# MicroMaster.net
KiCad netlist of a schematic drawn in EAGLE
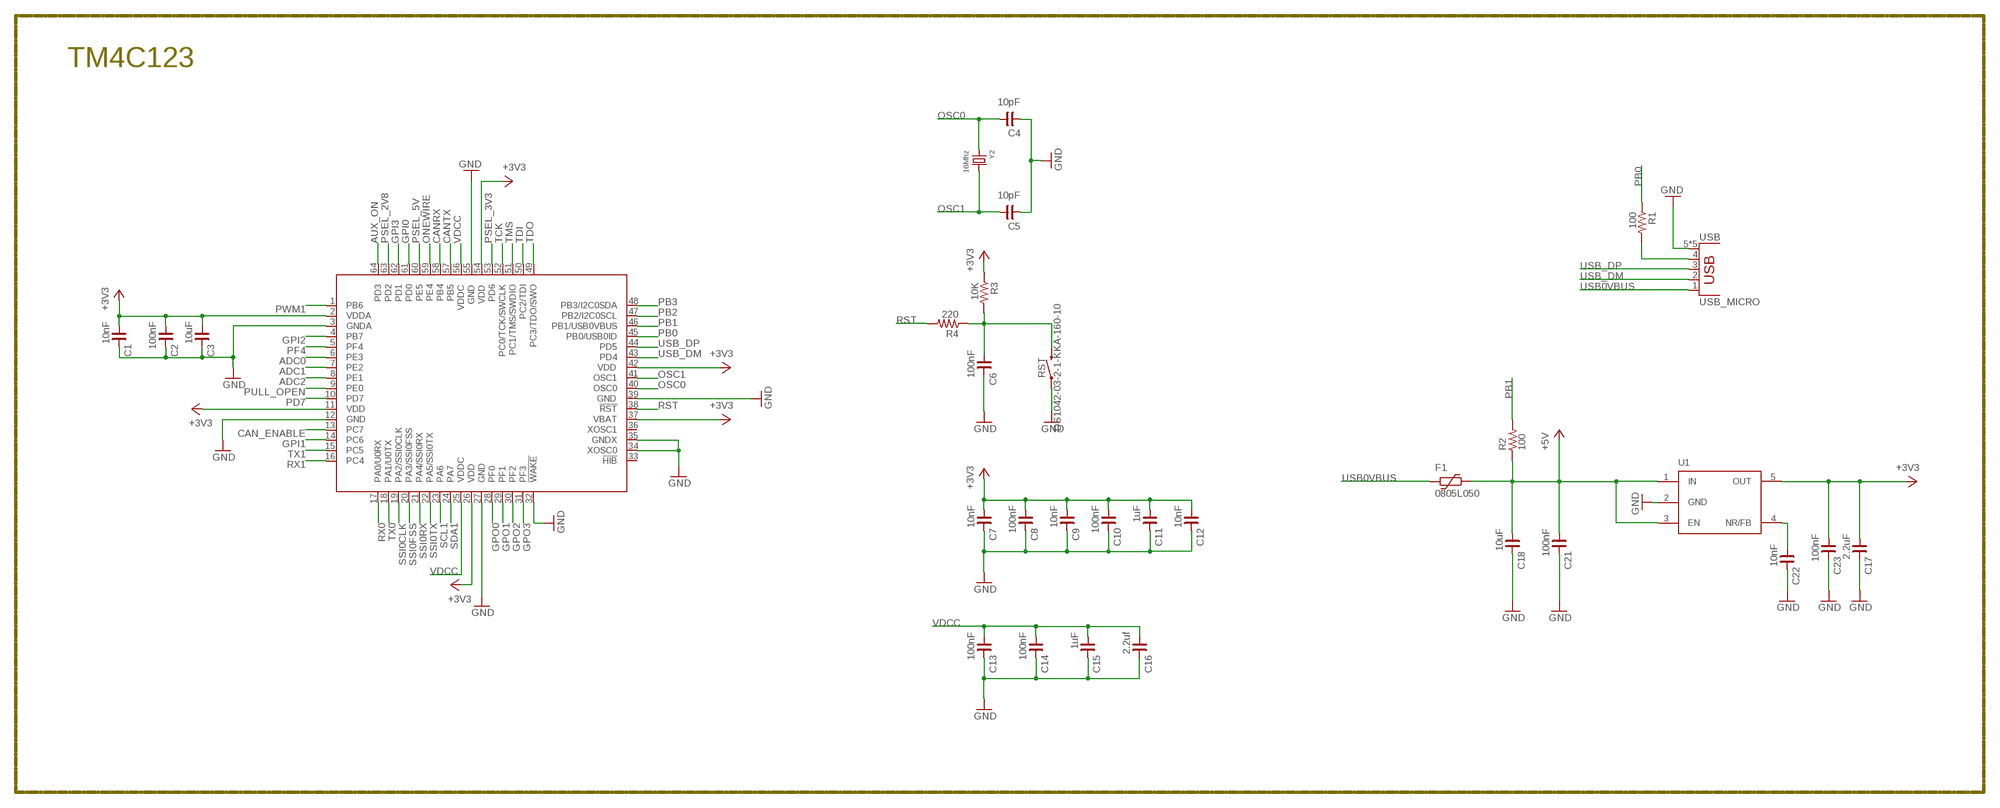
[diagram p0: schematic, sheet 1, part 1 of 3]
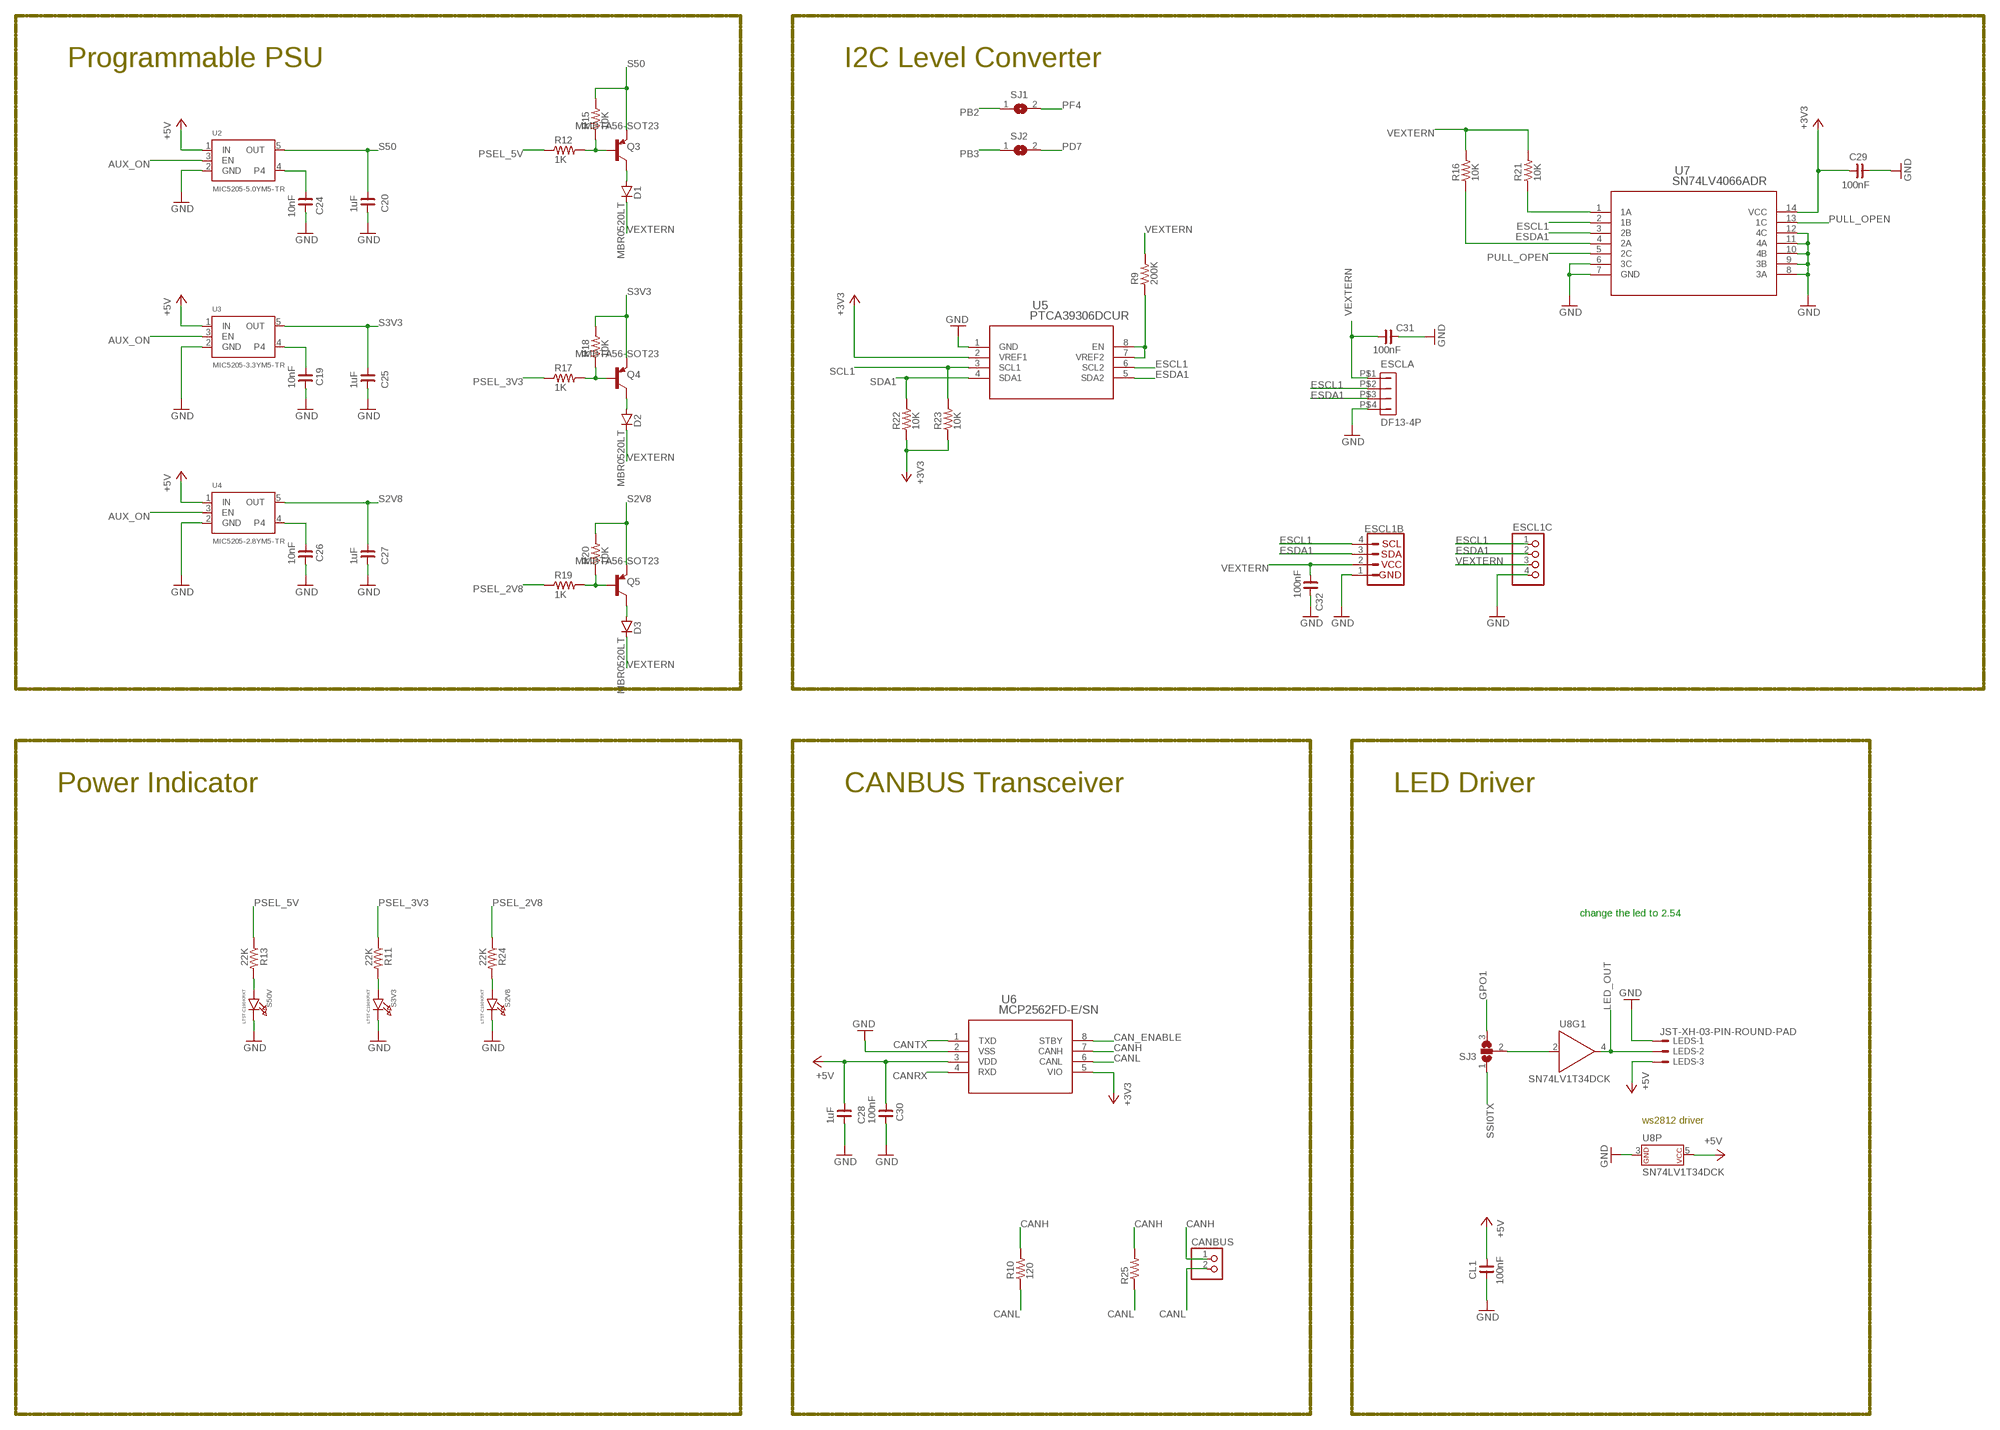
[diagram p1: schematic, sheet 1, part 2 of 3]
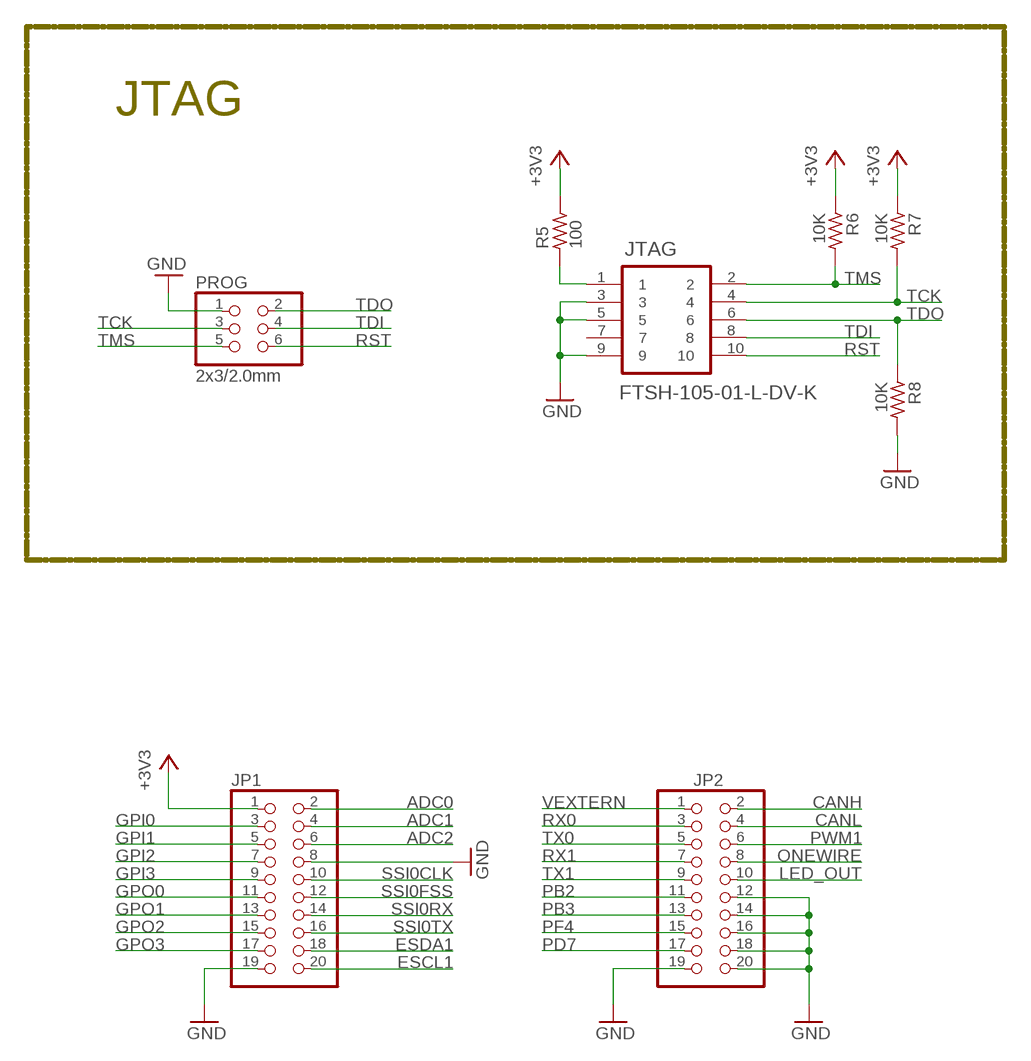
[diagram p2: schematic, sheet 1, part 3 of 3]

(export (version "E")
  (design (tool "Eeschema 10.0.6"))
  (components
    (comp (ref "C1")
      (value "10nF")
      (footprint "eagle-import:C0402")
      (libsource (lib "eagle-import") (part "C_0402"))
    )
    (comp (ref "C2")
      (value "100nF")
      (footprint "eagle-import:C0402")
      (libsource (lib "eagle-import") (part "C_0402"))
    )
    (comp (ref "C3")
      (value "10uF")
      (footprint "eagle-import:C0603")
      (libsource (lib "eagle-import") (part "C_0603"))
    )
    (comp (ref "C4")
      (value "10pF")
      (footprint "eagle-import:C0402")
      (libsource (lib "eagle-import") (part "C_0402"))
    )
    (comp (ref "C5")
      (value "10pF")
      (footprint "eagle-import:C0402")
      (libsource (lib "eagle-import") (part "C_0402"))
    )
    (comp (ref "C6")
      (value "100nF")
      (footprint "eagle-import:C0402")
      (libsource (lib "eagle-import") (part "C_0402"))
    )
    (comp (ref "C7")
      (value "10nF")
      (footprint "eagle-import:C0402")
      (libsource (lib "eagle-import") (part "C_0402"))
    )
    (comp (ref "C8")
      (value "100nF")
      (footprint "eagle-import:C0402")
      (libsource (lib "eagle-import") (part "C_0402"))
    )
    (comp (ref "C9")
      (value "10nF")
      (footprint "eagle-import:C0402")
      (libsource (lib "eagle-import") (part "C_0402"))
    )
    (comp (ref "C10")
      (value "100nF")
      (footprint "eagle-import:C0402")
      (libsource (lib "eagle-import") (part "C_0402"))
    )
    (comp (ref "C11")
      (value "1uF")
      (footprint "eagle-import:C0402")
      (libsource (lib "eagle-import") (part "C_0402"))
    )
    (comp (ref "C12")
      (value "10nF")
      (footprint "eagle-import:C0402")
      (libsource (lib "eagle-import") (part "C_0402"))
    )
    (comp (ref "C13")
      (value "100nF")
      (footprint "eagle-import:C0402")
      (libsource (lib "eagle-import") (part "C_0402"))
    )
    (comp (ref "C14")
      (value "100nF")
      (footprint "eagle-import:C0402")
      (libsource (lib "eagle-import") (part "C_0402"))
    )
    (comp (ref "C15")
      (value "1uF")
      (footprint "eagle-import:C0402")
      (libsource (lib "eagle-import") (part "C_0402"))
    )
    (comp (ref "C16")
      (value "2.2uf")
      (footprint "eagle-import:C0603")
      (libsource (lib "eagle-import") (part "C_0603"))
    )
    (comp (ref "C17")
      (value "2.2uF")
      (footprint "eagle-import:C0603")
      (libsource (lib "eagle-import") (part "C_0603"))
    )
    (comp (ref "C18")
      (value "10uF")
      (footprint "eagle-import:C0603")
      (libsource (lib "eagle-import") (part "C_0603"))
    )
    (comp (ref "C19")
      (value "10nF")
      (footprint "eagle-import:C0402")
      (libsource (lib "eagle-import") (part "C_0402"))
    )
    (comp (ref "C20")
      (value "1uF")
      (footprint "eagle-import:C0603")
      (libsource (lib "eagle-import") (part "C_0603"))
    )
    (comp (ref "C21")
      (value "100nF")
      (footprint "eagle-import:C0402")
      (libsource (lib "eagle-import") (part "C_0402"))
    )
    (comp (ref "C22")
      (value "10nF")
      (footprint "eagle-import:C0402")
      (libsource (lib "eagle-import") (part "C_0402"))
    )
    (comp (ref "C23")
      (value "100nF")
      (footprint "eagle-import:C0402")
      (libsource (lib "eagle-import") (part "C_0402"))
    )
    (comp (ref "C24")
      (value "10nF")
      (footprint "eagle-import:C0402")
      (libsource (lib "eagle-import") (part "C_0402"))
    )
    (comp (ref "C25")
      (value "1uF")
      (footprint "eagle-import:C0603")
      (libsource (lib "eagle-import") (part "C_0603"))
    )
    (comp (ref "C26")
      (value "10nF")
      (footprint "eagle-import:C0402")
      (libsource (lib "eagle-import") (part "C_0402"))
    )
    (comp (ref "C27")
      (value "1uF")
      (footprint "eagle-import:C0603")
      (libsource (lib "eagle-import") (part "C_0603"))
    )
    (comp (ref "C28")
      (value "1uF")
      (footprint "eagle-import:C0805")
      (libsource (lib "eagle-import") (part "C_0805"))
    )
    (comp (ref "C29")
      (value "100nF")
      (footprint "eagle-import:C0603")
      (libsource (lib "eagle-import") (part "C_0603"))
    )
    (comp (ref "C30")
      (value "100nF")
      (footprint "eagle-import:C0603")
      (libsource (lib "eagle-import") (part "C_0603"))
    )
    (comp (ref "C31")
      (value "100nF")
      (footprint "eagle-import:C0402")
      (libsource (lib "eagle-import") (part "C_0402"))
    )
    (comp (ref "C32")
      (value "100nF")
      (footprint "eagle-import:C0402")
      (libsource (lib "eagle-import") (part "C_0402"))
    )
    (comp (ref "CANBUS")
      (value "PINHD-1X02_2.54-S")
      (footprint "eagle-import:1X02-S")
      (libsource (lib "eagle-import") (part "PINHD-1X02_2.54-S"))
    )
    (comp (ref "CL1")
      (value "100nF")
      (footprint "eagle-import:C0402")
      (libsource (lib "eagle-import") (part "C_0402"))
    )
    (comp (ref "D1")
      (value "MBR0520LT")
      (footprint "eagle-import:SOD123")
      (libsource (lib "eagle-import") (part "MBR0520LT"))
    )
    (comp (ref "D2")
      (value "MBR0520LT")
      (footprint "eagle-import:SOD123")
      (libsource (lib "eagle-import") (part "MBR0520LT"))
    )
    (comp (ref "D3")
      (value "MBR0520LT")
      (footprint "eagle-import:SOD123")
      (libsource (lib "eagle-import") (part "MBR0520LT"))
    )
    (comp (ref "ESCL1B")
      (value "QWIIC_CONNECTORJS-1MM")
      (footprint "eagle-import:1X04_1MM_RA")
      (libsource (lib "eagle-import") (part "QWIIC_CONNECTORJS-1MM"))
    )
    (comp (ref "ESCL1C")
      (value "PINHD-1X04_2.54-S")
      (footprint "eagle-import:1X04-S")
      (libsource (lib "eagle-import") (part "PINHD-1X04_2.54-S"))
    )
    (comp (ref "ESCLA")
      (value "DF13-4P")
      (footprint "eagle-import:DF13-4P-1.25DSA")
      (libsource (lib "eagle-import") (part "DF13-4P-1.25DSA"))
    )
    (comp (ref "F1")
      (value "0805L050")
      (footprint "eagle-import:0805L")
      (fields (field (name "MF") "Littelfuse"))
      (libsource (lib "eagle-import") (part "?0805L050"))
    )
    (comp (ref "IC1")
      (value "TM4C123[7,G]XXPM")
      (footprint "eagle-import:PM_S-PQFP-G64")
      (libsource (lib "eagle-import") (part "TM4C123[7,G]XXPM"))
    )
    (comp (ref "JP1")
      (value "PINHD-2X10_2.54")
      (footprint "eagle-import:2X10")
      (libsource (lib "eagle-import") (part "PINHD-2X10_2.54"))
    )
    (comp (ref "JP2")
      (value "PINHD-2X10_2.54")
      (footprint "eagle-import:2X10")
      (libsource (lib "eagle-import") (part "PINHD-2X10_2.54"))
    )
    (comp (ref "JTAG")
      (value "FTSH-105-01-L-DV-K")
      (footprint "eagle-import:SAMTEC_FTSH-105-01-L-DV-K")
      (fields (field (name "MF") "Samtec"))
      (libsource (lib "eagle-import") (part "FTSH-105-01-L-DV-K"))
    )
    (comp (ref "LEDS")
      (value "JST-XH-03-PIN-ROUND-PAD")
      (footprint "eagle-import:JST-XH-03-PACKAGE-ROUND-PAD")
      (libsource (lib "eagle-import") (part "JST-XH-03-PIN-ROUND-PAD"))
    )
    (comp (ref "PROG")
      (value "2x3/2.0mm")
      (footprint "eagle-import:2X03M")
      (libsource (lib "eagle-import") (part "PINHD-2X03_2.00"))
    )
    (comp (ref "Q3")
      (value "MMBTA56-SOT23")
      (footprint "eagle-import:SOT23")
      (libsource (lib "eagle-import") (part "-?SOT23MMBTA56"))
    )
    (comp (ref "Q4")
      (value "MMBTA56-SOT23")
      (footprint "eagle-import:SOT23")
      (libsource (lib "eagle-import") (part "-?SOT23MMBTA56"))
    )
    (comp (ref "Q5")
      (value "MMBTA56-SOT23")
      (footprint "eagle-import:SOT23")
      (libsource (lib "eagle-import") (part "-?SOT23MMBTA56"))
    )
    (comp (ref "R1")
      (value "100")
      (footprint "eagle-import:R0402")
      (libsource (lib "eagle-import") (part "R_0402"))
    )
    (comp (ref "R2")
      (value "100")
      (footprint "eagle-import:R0402")
      (libsource (lib "eagle-import") (part "R_0402"))
    )
    (comp (ref "R3")
      (value "10K")
      (footprint "eagle-import:R0402")
      (libsource (lib "eagle-import") (part "R_0402"))
    )
    (comp (ref "R4")
      (value "220")
      (footprint "eagle-import:R0402")
      (libsource (lib "eagle-import") (part "R_0402"))
    )
    (comp (ref "R5")
      (value "100")
      (footprint "eagle-import:R0402")
      (libsource (lib "eagle-import") (part "R_0402"))
    )
    (comp (ref "R6")
      (value "10K")
      (footprint "eagle-import:R0402")
      (libsource (lib "eagle-import") (part "R_0402"))
    )
    (comp (ref "R7")
      (value "10K")
      (footprint "eagle-import:R0402")
      (libsource (lib "eagle-import") (part "R_0402"))
    )
    (comp (ref "R8")
      (value "10K")
      (footprint "eagle-import:R0402")
      (libsource (lib "eagle-import") (part "R_0402"))
    )
    (comp (ref "R9")
      (value "200K")
      (footprint "eagle-import:R0402")
      (libsource (lib "eagle-import") (part "R_0402"))
    )
    (comp (ref "R10")
      (value "120")
      (footprint "eagle-import:R0603")
      (libsource (lib "eagle-import") (part "R_0603"))
    )
    (comp (ref "R11")
      (value "22K")
      (footprint "eagle-import:R0402")
      (libsource (lib "eagle-import") (part "R_0402"))
    )
    (comp (ref "R12")
      (value "1K")
      (footprint "eagle-import:R0402")
      (libsource (lib "eagle-import") (part "R_0402"))
    )
    (comp (ref "R13")
      (value "22K")
      (footprint "eagle-import:R0402")
      (libsource (lib "eagle-import") (part "R_0402"))
    )
    (comp (ref "R15")
      (value "10K")
      (footprint "eagle-import:R0402")
      (libsource (lib "eagle-import") (part "R_0402"))
    )
    (comp (ref "R16")
      (value "10K")
      (footprint "eagle-import:R0402")
      (libsource (lib "eagle-import") (part "R_0402"))
    )
    (comp (ref "R17")
      (value "1K")
      (footprint "eagle-import:R0402")
      (libsource (lib "eagle-import") (part "R_0402"))
    )
    (comp (ref "R18")
      (value "10K")
      (footprint "eagle-import:R0402")
      (libsource (lib "eagle-import") (part "R_0402"))
    )
    (comp (ref "R19")
      (value "1K")
      (footprint "eagle-import:R0402")
      (libsource (lib "eagle-import") (part "R_0402"))
    )
    (comp (ref "R20")
      (value "10K")
      (footprint "eagle-import:R0402")
      (libsource (lib "eagle-import") (part "R_0402"))
    )
    (comp (ref "R21")
      (value "10K")
      (footprint "eagle-import:R0402")
      (libsource (lib "eagle-import") (part "R_0402"))
    )
    (comp (ref "R22")
      (value "10K")
      (footprint "eagle-import:R0402")
      (libsource (lib "eagle-import") (part "R_0402"))
    )
    (comp (ref "R23")
      (value "10K")
      (footprint "eagle-import:R0402")
      (libsource (lib "eagle-import") (part "R_0402"))
    )
    (comp (ref "R24")
      (value "22K")
      (footprint "eagle-import:R0402")
      (libsource (lib "eagle-import") (part "R_0402"))
    )
    (comp (ref "R25")
      (value "R-US_0204/5")
      (footprint "eagle-import:0204_5")
      (libsource (lib "eagle-import") (part "R-US_0204/5"))
    )
    (comp (ref "RST")
      (value "DS1042-03-2-1-KKA-160-10")
      (footprint "eagle-import:DS1042-03-2-1")
      (libsource (lib "eagle-import") (part "DS1042-03-2-1"))
    )
    (comp (ref "S2V8")
      (value "LTST-C190KRKT")
      (footprint "eagle-import:CHIPLED_0603")
      (libsource (lib "eagle-import") (part "LED0603"))
    )
    (comp (ref "S3V3")
      (value "LTST-C190KRKT")
      (footprint "eagle-import:CHIPLED_0603")
      (libsource (lib "eagle-import") (part "LED0603"))
    )
    (comp (ref "S50V")
      (value "LTST-C190KRKT")
      (footprint "eagle-import:CHIPLED_0603")
      (libsource (lib "eagle-import") (part "LED0603"))
    )
    (comp (ref "SJ1")
      (value "SOLDERJUMPERCLOSED")
      (footprint "eagle-import:SOLDERJUMPER_CLOSEDWIRE")
      (libsource (lib "eagle-import") (part "SOLDERJUMPERCLOSED"))
    )
    (comp (ref "SJ2")
      (value "SOLDERJUMPERCLOSED")
      (footprint "eagle-import:SOLDERJUMPER_CLOSEDWIRE")
      (libsource (lib "eagle-import") (part "SOLDERJUMPERCLOSED"))
    )
    (comp (ref "SJ3")
      (value "SJ2W")
      (footprint "eagle-import:SJ_2")
      (libsource (lib "eagle-import") (part "SJ2W"))
    )
    (comp (ref "U1")
      (value "TPS73633")
      (footprint "eagle-import:SOT23-5L")
      (libsource (lib "eagle-import") (part "TPS73633"))
    )
    (comp (ref "U2")
      (value "MIC5205-5.0YM5-TR")
      (footprint "eagle-import:SOT23-5")
      (libsource (lib "eagle-import") (part "VREG_SOT23-5"))
    )
    (comp (ref "U3")
      (value "MIC5205-3.3YM5-TR")
      (footprint "eagle-import:SOT23-5")
      (libsource (lib "eagle-import") (part "VREG_SOT23-5"))
    )
    (comp (ref "U4")
      (value "MIC5205-2.8YM5-TR")
      (footprint "eagle-import:SOT23-5")
      (libsource (lib "eagle-import") (part "VREG_SOT23-5"))
    )
    (comp (ref "U5")
      (value "PTCA39306DCUR")
      (footprint "eagle-import:VSSOP8_PTCA39306DCUR_TEX")
      (fields (field (name "COPYRIGHT") "Copyright (C) 2021 Ultra Librarian. All rights reserved."))
      (libsource (lib "eagle-import") (part "PTCA39306DCUR"))
    )
    (comp (ref "U6")
      (value "MCP2562FD-E/SN")
      (footprint "eagle-import:SOIC8-N_MC_MCH")
      (fields (field (name "COPYRIGHT") "Copyright (C) 2021 Ultra Librarian. All rights reserved."))
      (libsource (lib "eagle-import") (part "MCP2562FD-E/SN"))
    )
    (comp (ref "U7")
      (value "SN74LV4066ADR")
      (footprint "eagle-import:D14")
      (fields (field (name "COPYRIGHT") "Copyright (C) 2021 Ultra Librarian. All rights reserved."))
      (libsource (lib "eagle-import") (part "SN74LV4066ADR"))
    )
    (comp (ref "U8")
      (value "SN74LV1T34DCK")
      (footprint "eagle-import:SC70-5")
      (libsource (lib "eagle-import") (part "SN74LV1T34DCK"))
    )
    (comp (ref "USB")
      (value "USB_MICRO")
      (footprint "eagle-import:USB_MICRO_MOLEX_FULL")
      (libsource (lib "eagle-import") (part "USB_MICRO"))
    )
    (comp (ref "Y2")
      (value "16Mhz")
      (footprint "eagle-import:6X3.3MM")
      (libsource (lib "eagle-import") (part "CRYSTAL.6X3.3MM"))
    )
  )
  (nets
    (net (code "1") (name "+3V3") (class "Default")
      (node (ref "C1") (pin "1") (pinfunction "1_1") (pintype "passive"))
      (node (ref "C10") (pin "1") (pinfunction "1_1") (pintype "passive"))
      (node (ref "C11") (pin "1") (pinfunction "1_1") (pintype "passive"))
      (node (ref "C12") (pin "1") (pinfunction "1_1") (pintype "passive"))
      (node (ref "C17") (pin "1") (pinfunction "1_1") (pintype "passive"))
      (node (ref "C2") (pin "1") (pinfunction "1_1") (pintype "passive"))
      (node (ref "C23") (pin "1") (pinfunction "1_1") (pintype "passive"))
      (node (ref "C29") (pin "1") (pinfunction "1_1") (pintype "passive"))
      (node (ref "C3") (pin "1") (pinfunction "1_1") (pintype "passive"))
      (node (ref "C7") (pin "1") (pinfunction "1_1") (pintype "passive"))
      (node (ref "C8") (pin "1") (pinfunction "1_1") (pintype "passive"))
      (node (ref "C9") (pin "1") (pinfunction "1_1") (pintype "passive"))
      (node (ref "IC1") (pin "11") (pinfunction "VDD_11") (pintype "bidirectional"))
      (node (ref "IC1") (pin "2") (pinfunction "VDDA_2") (pintype "bidirectional"))
      (node (ref "IC1") (pin "26") (pinfunction "VDD_26") (pintype "bidirectional"))
      (node (ref "IC1") (pin "37") (pinfunction "VBAT_37") (pintype "bidirectional"))
      (node (ref "IC1") (pin "42") (pinfunction "VDD_42") (pintype "bidirectional"))
      (node (ref "IC1") (pin "54") (pinfunction "VDD_54") (pintype "bidirectional"))
      (node (ref "JP1") (pin "1") (pinfunction "1_1") (pintype "passive"))
      (node (ref "R22") (pin "1") (pinfunction "1_1") (pintype "passive"))
      (node (ref "R23") (pin "1") (pinfunction "1_1") (pintype "passive"))
      (node (ref "R3") (pin "1") (pinfunction "1_1") (pintype "passive"))
      (node (ref "R5") (pin "2") (pinfunction "2_2") (pintype "passive"))
      (node (ref "R6") (pin "1") (pinfunction "1_1") (pintype "passive"))
      (node (ref "R7") (pin "1") (pinfunction "1_1") (pintype "passive"))
      (node (ref "U1") (pin "5") (pinfunction "OUT_5") (pintype "bidirectional"))
      (node (ref "U5") (pin "2") (pinfunction "VREF1_2") (pintype "power_in"))
      (node (ref "U6") (pin "5") (pinfunction "VIO_5") (pintype "power_in"))
      (node (ref "U7") (pin "14") (pinfunction "VCC_14") (pintype "power_in"))
    )
    (net (code "2") (name "+5V") (class "Default")
      (node (ref "C18") (pin "1") (pinfunction "1_1") (pintype "passive"))
      (node (ref "C21") (pin "1") (pinfunction "1_1") (pintype "passive"))
      (node (ref "C28") (pin "1") (pinfunction "1_1") (pintype "passive"))
      (node (ref "C30") (pin "1") (pinfunction "1_1") (pintype "passive"))
      (node (ref "CL1") (pin "2") (pinfunction "2_2") (pintype "passive"))
      (node (ref "F1") (pin "1") (pinfunction "1_1") (pintype "passive"))
      (node (ref "LEDS") (pin "3") (pinfunction "S_3") (pintype "passive"))
      (node (ref "R2") (pin "1") (pinfunction "1_1") (pintype "passive"))
      (node (ref "U1") (pin "1") (pinfunction "IN_1") (pintype "bidirectional"))
      (node (ref "U1") (pin "3") (pinfunction "EN_3") (pintype "bidirectional"))
      (node (ref "U2") (pin "1") (pinfunction "IN_1") (pintype "bidirectional"))
      (node (ref "U3") (pin "1") (pinfunction "IN_1") (pintype "bidirectional"))
      (node (ref "U4") (pin "1") (pinfunction "IN_1") (pintype "bidirectional"))
      (node (ref "U6") (pin "3") (pinfunction "VDD_3") (pintype "power_in"))
      (node (ref "U8") (pin "5") (pinfunction "P$V+_5") (pintype "bidirectional"))
    )
    (net (code "3") (name "/ADC0") (class "Default")
      (node (ref "IC1") (pin "6") (pinfunction "PE3_6") (pintype "bidirectional"))
      (node (ref "JP1") (pin "2") (pinfunction "2_2") (pintype "passive"))
    )
    (net (code "4") (name "/ADC1") (class "Default")
      (node (ref "IC1") (pin "7") (pinfunction "PE2_7") (pintype "bidirectional"))
      (node (ref "JP1") (pin "4") (pinfunction "4_4") (pintype "passive"))
    )
    (net (code "5") (name "/ADC2") (class "Default")
      (node (ref "IC1") (pin "8") (pinfunction "PE1_8") (pintype "bidirectional"))
      (node (ref "JP1") (pin "6") (pinfunction "6_6") (pintype "passive"))
    )
    (net (code "6") (name "/AUX_ON") (class "Default")
      (node (ref "IC1") (pin "64") (pinfunction "PD3_64") (pintype "bidirectional"))
      (node (ref "U2") (pin "3") (pinfunction "EN_3") (pintype "bidirectional"))
      (node (ref "U3") (pin "3") (pinfunction "EN_3") (pintype "bidirectional"))
      (node (ref "U4") (pin "3") (pinfunction "EN_3") (pintype "bidirectional"))
    )
    (net (code "7") (name "/CANH") (class "Default")
      (node (ref "CANBUS") (pin "1") (pinfunction "1_1") (pintype "passive"))
      (node (ref "JP2") (pin "2") (pinfunction "2_2") (pintype "passive"))
      (node (ref "R10") (pin "2") (pinfunction "2_2") (pintype "passive"))
      (node (ref "R25") (pin "2") (pinfunction "2_2") (pintype "passive"))
      (node (ref "U6") (pin "7") (pinfunction "CANH_7") (pintype "bidirectional"))
    )
    (net (code "8") (name "/CANL") (class "Default")
      (node (ref "CANBUS") (pin "2") (pinfunction "2_2") (pintype "passive"))
      (node (ref "JP2") (pin "4") (pinfunction "4_4") (pintype "passive"))
      (node (ref "R10") (pin "1") (pinfunction "1_1") (pintype "passive"))
      (node (ref "R25") (pin "1") (pinfunction "1_1") (pintype "passive"))
      (node (ref "U6") (pin "6") (pinfunction "CANL_6") (pintype "bidirectional"))
    )
    (net (code "9") (name "/CANRX") (class "Default")
      (node (ref "IC1") (pin "58") (pinfunction "PB4_58") (pintype "bidirectional"))
      (node (ref "U6") (pin "4") (pinfunction "RXD_4") (pintype "output"))
    )
    (net (code "10") (name "/CANTX") (class "Default")
      (node (ref "IC1") (pin "57") (pinfunction "PB5_57") (pintype "bidirectional"))
      (node (ref "U6") (pin "1") (pinfunction "TXD_1") (pintype "input"))
    )
    (net (code "11") (name "/CAN_ENABLE") (class "Default")
      (node (ref "IC1") (pin "13") (pinfunction "PC7_13") (pintype "bidirectional"))
      (node (ref "U6") (pin "8") (pinfunction "STBY_8") (pintype "input"))
    )
    (net (code "12") (name "/ESCL1") (class "Default")
      (node (ref "ESCL1B") (pin "4") (pinfunction "4_4") (pintype "passive"))
      (node (ref "ESCL1C") (pin "1") (pinfunction "1_1") (pintype "passive"))
      (node (ref "ESCLA") (pin "P$2") (pinfunction "2_P$2") (pintype "passive"))
      (node (ref "JP1") (pin "20") (pinfunction "20_20") (pintype "passive"))
      (node (ref "U5") (pin "6") (pinfunction "SCL2_6") (pintype "bidirectional"))
      (node (ref "U7") (pin "2") (pinfunction "1B_2") (pintype "input"))
    )
    (net (code "13") (name "/ESDA1") (class "Default")
      (node (ref "ESCL1B") (pin "3") (pinfunction "3_3") (pintype "passive"))
      (node (ref "ESCL1C") (pin "2") (pinfunction "2_2") (pintype "passive"))
      (node (ref "ESCLA") (pin "P$3") (pinfunction "3_P$3") (pintype "passive"))
      (node (ref "JP1") (pin "18") (pinfunction "18_18") (pintype "passive"))
      (node (ref "U5") (pin "5") (pinfunction "SDA2_5") (pintype "bidirectional"))
      (node (ref "U7") (pin "3") (pinfunction "2B_3") (pintype "input"))
    )
    (net (code "14") (name "/GPI0") (class "Default")
      (node (ref "IC1") (pin "61") (pinfunction "PD0_61") (pintype "bidirectional"))
      (node (ref "JP1") (pin "3") (pinfunction "3_3") (pintype "passive"))
    )
    (net (code "15") (name "/GPI1") (class "Default")
      (node (ref "IC1") (pin "14") (pinfunction "PC6_14") (pintype "bidirectional"))
      (node (ref "JP1") (pin "5") (pinfunction "5_5") (pintype "passive"))
    )
    (net (code "16") (name "/GPI2") (class "Default")
      (node (ref "IC1") (pin "4") (pinfunction "PB7_4") (pintype "bidirectional"))
      (node (ref "JP1") (pin "7") (pinfunction "7_7") (pintype "passive"))
    )
    (net (code "17") (name "/GPI3") (class "Default")
      (node (ref "IC1") (pin "62") (pinfunction "PD1_62") (pintype "bidirectional"))
      (node (ref "JP1") (pin "9") (pinfunction "9_9") (pintype "passive"))
    )
    (net (code "18") (name "/GPO0") (class "Default")
      (node (ref "IC1") (pin "28") (pinfunction "PF0_28") (pintype "bidirectional"))
      (node (ref "JP1") (pin "11") (pinfunction "11_11") (pintype "passive"))
    )
    (net (code "19") (name "/GPO1") (class "Default")
      (node (ref "IC1") (pin "29") (pinfunction "PF1_29") (pintype "bidirectional"))
      (node (ref "JP1") (pin "13") (pinfunction "13_13") (pintype "passive"))
      (node (ref "SJ3") (pin "3") (pinfunction "3_3") (pintype "passive"))
    )
    (net (code "20") (name "/GPO2") (class "Default")
      (node (ref "IC1") (pin "30") (pinfunction "PF2_30") (pintype "bidirectional"))
      (node (ref "JP1") (pin "15") (pinfunction "15_15") (pintype "passive"))
    )
    (net (code "21") (name "/GPO3") (class "Default")
      (node (ref "IC1") (pin "31") (pinfunction "PF3_31") (pintype "bidirectional"))
      (node (ref "JP1") (pin "17") (pinfunction "17_17") (pintype "passive"))
    )
    (net (code "22") (name "/LED_OUT") (class "Default")
      (node (ref "JP2") (pin "10") (pinfunction "10_10") (pintype "passive"))
      (node (ref "LEDS") (pin "2") (pinfunction "S_2") (pintype "passive"))
      (node (ref "U8") (pin "4") (pinfunction "Y_4") (pintype "bidirectional"))
    )
    (net (code "23") (name "/ONEWIRE") (class "Default")
      (node (ref "IC1") (pin "59") (pinfunction "PE4_59") (pintype "bidirectional"))
      (node (ref "JP2") (pin "8") (pinfunction "8_8") (pintype "passive"))
    )
    (net (code "24") (name "/OSC0") (class "Default")
      (node (ref "C4") (pin "2") (pinfunction "2_2") (pintype "passive"))
      (node (ref "IC1") (pin "40") (pinfunction "OSC0_40") (pintype "bidirectional"))
      (node (ref "Y2") (pin "1") (pinfunction "1_1") (pintype "passive"))
    )
    (net (code "25") (name "/OSC1") (class "Default")
      (node (ref "C5") (pin "2") (pinfunction "2_2") (pintype "passive"))
      (node (ref "IC1") (pin "41") (pinfunction "OSC1_41") (pintype "bidirectional"))
      (node (ref "Y2") (pin "2") (pinfunction "2_2") (pintype "passive"))
    )
    (net (code "26") (name "/PB0") (class "Default")
      (node (ref "IC1") (pin "45") (pinfunction "PB0/USB0ID_45") (pintype "bidirectional"))
      (node (ref "R1") (pin "1") (pinfunction "1_1") (pintype "passive"))
    )
    (net (code "27") (name "/PB1") (class "Default")
      (node (ref "IC1") (pin "46") (pinfunction "PB1/USB0VBUS_46") (pintype "bidirectional"))
      (node (ref "R2") (pin "2") (pinfunction "2_2") (pintype "passive"))
    )
    (net (code "28") (name "/PB2") (class "Default")
      (node (ref "IC1") (pin "47") (pinfunction "PB2/I2C0SCL_47") (pintype "bidirectional"))
      (node (ref "JP2") (pin "11") (pinfunction "11_11") (pintype "passive"))
      (node (ref "SJ1") (pin "1") (pinfunction "1_1") (pintype "passive"))
    )
    (net (code "29") (name "/PB3") (class "Default")
      (node (ref "IC1") (pin "48") (pinfunction "PB3/I2C0SDA_48") (pintype "bidirectional"))
      (node (ref "JP2") (pin "13") (pinfunction "13_13") (pintype "passive"))
      (node (ref "SJ2") (pin "1") (pinfunction "1_1") (pintype "passive"))
    )
    (net (code "30") (name "/PD7") (class "Default")
      (node (ref "IC1") (pin "10") (pinfunction "PD7_10") (pintype "bidirectional"))
      (node (ref "JP2") (pin "17") (pinfunction "17_17") (pintype "passive"))
      (node (ref "SJ2") (pin "2") (pinfunction "2_2") (pintype "passive"))
    )
    (net (code "31") (name "/PF4") (class "Default")
      (node (ref "IC1") (pin "5") (pinfunction "PF4_5") (pintype "bidirectional"))
      (node (ref "JP2") (pin "15") (pinfunction "15_15") (pintype "passive"))
      (node (ref "SJ1") (pin "2") (pinfunction "2_2") (pintype "passive"))
    )
    (net (code "32") (name "/PSEL_2V8") (class "Default")
      (node (ref "IC1") (pin "63") (pinfunction "PD2_63") (pintype "bidirectional"))
      (node (ref "R19") (pin "1") (pinfunction "1_1") (pintype "passive"))
      (node (ref "R24") (pin "1") (pinfunction "1_1") (pintype "passive"))
    )
    (net (code "33") (name "/PSEL_3V3") (class "Default")
      (node (ref "IC1") (pin "53") (pinfunction "PD6_53") (pintype "bidirectional"))
      (node (ref "R11") (pin "1") (pinfunction "1_1") (pintype "passive"))
      (node (ref "R17") (pin "1") (pinfunction "1_1") (pintype "passive"))
    )
    (net (code "34") (name "/PSEL_5V") (class "Default")
      (node (ref "IC1") (pin "60") (pinfunction "PE5_60") (pintype "bidirectional"))
      (node (ref "R12") (pin "1") (pinfunction "1_1") (pintype "passive"))
      (node (ref "R13") (pin "1") (pinfunction "1_1") (pintype "passive"))
    )
    (net (code "35") (name "/PULL_OPEN") (class "Default")
      (node (ref "IC1") (pin "9") (pinfunction "PE0_9") (pintype "bidirectional"))
      (node (ref "U7") (pin "13") (pinfunction "1C_13") (pintype "input"))
      (node (ref "U7") (pin "5") (pinfunction "2C_5") (pintype "input"))
    )
    (net (code "36") (name "/PWM1") (class "Default")
      (node (ref "IC1") (pin "1") (pinfunction "PB6_1") (pintype "bidirectional"))
      (node (ref "JP2") (pin "6") (pinfunction "6_6") (pintype "passive"))
    )
    (net (code "37") (name "/RST") (class "Default")
      (node (ref "IC1") (pin "38") (pinfunction "~{RST}_38") (pintype "bidirectional"))
      (node (ref "JTAG") (pin "10") (pinfunction "10_10") (pintype "passive"))
      (node (ref "PROG") (pin "6") (pinfunction "6_6") (pintype "passive"))
      (node (ref "R4") (pin "2") (pinfunction "2_2") (pintype "passive"))
    )
    (net (code "38") (name "/RX0") (class "Default")
      (node (ref "IC1") (pin "17") (pinfunction "PA0/U0RX_17") (pintype "bidirectional"))
      (node (ref "JP2") (pin "3") (pinfunction "3_3") (pintype "passive"))
    )
    (net (code "39") (name "/RX1") (class "Default")
      (node (ref "IC1") (pin "16") (pinfunction "PC4_16") (pintype "bidirectional"))
      (node (ref "JP2") (pin "7") (pinfunction "7_7") (pintype "passive"))
    )
    (net (code "40") (name "/S2V8") (class "Default")
      (node (ref "C27") (pin "1") (pinfunction "1_1") (pintype "passive"))
      (node (ref "Q5") (pin "2") (pinfunction "E_2") (pintype "passive"))
      (node (ref "R20") (pin "2") (pinfunction "2_2") (pintype "passive"))
      (node (ref "U4") (pin "5") (pinfunction "OUT_5") (pintype "bidirectional"))
    )
    (net (code "41") (name "/S3V3") (class "Default")
      (node (ref "C25") (pin "1") (pinfunction "1_1") (pintype "passive"))
      (node (ref "Q4") (pin "2") (pinfunction "E_2") (pintype "passive"))
      (node (ref "R18") (pin "2") (pinfunction "2_2") (pintype "passive"))
      (node (ref "U3") (pin "5") (pinfunction "OUT_5") (pintype "bidirectional"))
    )
    (net (code "42") (name "/S50") (class "Default")
      (node (ref "C20") (pin "1") (pinfunction "1_1") (pintype "passive"))
      (node (ref "Q3") (pin "2") (pinfunction "E_2") (pintype "passive"))
      (node (ref "R15") (pin "2") (pinfunction "2_2") (pintype "passive"))
      (node (ref "U2") (pin "5") (pinfunction "OUT_5") (pintype "bidirectional"))
    )
    (net (code "43") (name "/SCL1") (class "Default")
      (node (ref "IC1") (pin "23") (pinfunction "PA6_23") (pintype "bidirectional"))
      (node (ref "R23") (pin "2") (pinfunction "2_2") (pintype "passive"))
      (node (ref "U5") (pin "3") (pinfunction "SCL1_3") (pintype "bidirectional"))
    )
    (net (code "44") (name "/SDA1") (class "Default")
      (node (ref "IC1") (pin "24") (pinfunction "PA7_24") (pintype "bidirectional"))
      (node (ref "R22") (pin "2") (pinfunction "2_2") (pintype "passive"))
      (node (ref "U5") (pin "4") (pinfunction "SDA1_4") (pintype "bidirectional"))
    )
    (net (code "45") (name "/SSI0CLK") (class "Default")
      (node (ref "IC1") (pin "19") (pinfunction "PA2/SSI0CLK_19") (pintype "bidirectional"))
      (node (ref "JP1") (pin "10") (pinfunction "10_10") (pintype "passive"))
    )
    (net (code "46") (name "/SSI0FSS") (class "Default")
      (node (ref "IC1") (pin "20") (pinfunction "PA3/SSI0FSS_20") (pintype "bidirectional"))
      (node (ref "JP1") (pin "12") (pinfunction "12_12") (pintype "passive"))
    )
    (net (code "47") (name "/SSI0RX") (class "Default")
      (node (ref "IC1") (pin "21") (pinfunction "PA4/SSI0RX_21") (pintype "bidirectional"))
      (node (ref "JP1") (pin "14") (pinfunction "14_14") (pintype "passive"))
    )
    (net (code "48") (name "/SSI0TX") (class "Default")
      (node (ref "IC1") (pin "22") (pinfunction "PA5/SSI0TX_22") (pintype "bidirectional"))
      (node (ref "JP1") (pin "16") (pinfunction "16_16") (pintype "passive"))
      (node (ref "SJ3") (pin "1") (pinfunction "1_1") (pintype "passive"))
    )
    (net (code "49") (name "/TCK") (class "Default")
      (node (ref "IC1") (pin "52") (pinfunction "PC0/TCK/SWCLK_52") (pintype "bidirectional"))
      (node (ref "JTAG") (pin "4") (pinfunction "4_4") (pintype "passive"))
      (node (ref "PROG") (pin "3") (pinfunction "3_3") (pintype "passive"))
      (node (ref "R7") (pin "2") (pinfunction "2_2") (pintype "passive"))
    )
    (net (code "50") (name "/TDI") (class "Default")
      (node (ref "IC1") (pin "50") (pinfunction "PC2/TDI_50") (pintype "bidirectional"))
      (node (ref "JTAG") (pin "8") (pinfunction "8_8") (pintype "passive"))
      (node (ref "PROG") (pin "4") (pinfunction "4_4") (pintype "passive"))
    )
    (net (code "51") (name "/TDO") (class "Default")
      (node (ref "IC1") (pin "49") (pinfunction "PC3/TDO/SWO_49") (pintype "bidirectional"))
      (node (ref "JTAG") (pin "6") (pinfunction "6_6") (pintype "passive"))
      (node (ref "PROG") (pin "2") (pinfunction "2_2") (pintype "passive"))
      (node (ref "R8") (pin "1") (pinfunction "1_1") (pintype "passive"))
    )
    (net (code "52") (name "/TMS") (class "Default")
      (node (ref "IC1") (pin "51") (pinfunction "PC1/TMS/SWDIO_51") (pintype "bidirectional"))
      (node (ref "JTAG") (pin "2") (pinfunction "2_2") (pintype "passive"))
      (node (ref "PROG") (pin "5") (pinfunction "5_5") (pintype "passive"))
      (node (ref "R6") (pin "2") (pinfunction "2_2") (pintype "passive"))
    )
    (net (code "53") (name "/TX0") (class "Default")
      (node (ref "IC1") (pin "18") (pinfunction "PA1/U0TX_18") (pintype "bidirectional"))
      (node (ref "JP2") (pin "5") (pinfunction "5_5") (pintype "passive"))
    )
    (net (code "54") (name "/TX1") (class "Default")
      (node (ref "IC1") (pin "15") (pinfunction "PC5_15") (pintype "bidirectional"))
      (node (ref "JP2") (pin "9") (pinfunction "9_9") (pintype "passive"))
    )
    (net (code "55") (name "/USB0VBUS") (class "Default")
      (node (ref "F1") (pin "2") (pinfunction "2_2") (pintype "passive"))
      (node (ref "USB") (pin "1") (pinfunction "VBUS_1") (pintype "bidirectional"))
    )
    (net (code "56") (name "/USB_DM") (class "Default")
      (node (ref "IC1") (pin "43") (pinfunction "PD4_43") (pintype "bidirectional"))
      (node (ref "USB") (pin "2") (pinfunction "D-_2") (pintype "bidirectional"))
    )
    (net (code "57") (name "/USB_DP") (class "Default")
      (node (ref "IC1") (pin "44") (pinfunction "PD5_44") (pintype "bidirectional"))
      (node (ref "USB") (pin "3") (pinfunction "D+_3") (pintype "bidirectional"))
    )
    (net (code "58") (name "/VDCC") (class "Default")
      (node (ref "C13") (pin "1") (pinfunction "1_1") (pintype "passive"))
      (node (ref "C14") (pin "1") (pinfunction "1_1") (pintype "passive"))
      (node (ref "C15") (pin "1") (pinfunction "1_1") (pintype "passive"))
      (node (ref "C16") (pin "1") (pinfunction "1_1") (pintype "passive"))
      (node (ref "IC1") (pin "25") (pinfunction "VDDC_25") (pintype "bidirectional"))
      (node (ref "IC1") (pin "56") (pinfunction "VDDC_56") (pintype "bidirectional"))
    )
    (net (code "59") (name "/VEXTERN") (class "Default")
      (node (ref "C31") (pin "1") (pinfunction "1_1") (pintype "passive"))
      (node (ref "C32") (pin "1") (pinfunction "1_1") (pintype "passive"))
      (node (ref "D1") (pin "C") (pinfunction "C_C") (pintype "passive"))
      (node (ref "D2") (pin "C") (pinfunction "C_C") (pintype "passive"))
      (node (ref "D3") (pin "C") (pinfunction "C_C") (pintype "passive"))
      (node (ref "ESCL1B") (pin "2") (pinfunction "2_2") (pintype "power_in"))
      (node (ref "ESCL1C") (pin "3") (pinfunction "3_3") (pintype "passive"))
      (node (ref "ESCLA") (pin "P$1") (pinfunction "1_P$1") (pintype "passive"))
      (node (ref "JP2") (pin "1") (pinfunction "1_1") (pintype "passive"))
      (node (ref "R16") (pin "2") (pinfunction "2_2") (pintype "passive"))
      (node (ref "R21") (pin "2") (pinfunction "2_2") (pintype "passive"))
      (node (ref "R9") (pin "2") (pinfunction "2_2") (pintype "passive"))
    )
    (net (code "60") (name "GND") (class "Default")
      (node (ref "C1") (pin "2") (pinfunction "2_2") (pintype "passive"))
      (node (ref "C10") (pin "2") (pinfunction "2_2") (pintype "passive"))
      (node (ref "C11") (pin "2") (pinfunction "2_2") (pintype "passive"))
      (node (ref "C12") (pin "2") (pinfunction "2_2") (pintype "passive"))
      (node (ref "C13") (pin "2") (pinfunction "2_2") (pintype "passive"))
      (node (ref "C14") (pin "2") (pinfunction "2_2") (pintype "passive"))
      (node (ref "C15") (pin "2") (pinfunction "2_2") (pintype "passive"))
      (node (ref "C16") (pin "2") (pinfunction "2_2") (pintype "passive"))
      (node (ref "C17") (pin "2") (pinfunction "2_2") (pintype "passive"))
      (node (ref "C18") (pin "2") (pinfunction "2_2") (pintype "passive"))
      (node (ref "C19") (pin "2") (pinfunction "2_2") (pintype "passive"))
      (node (ref "C2") (pin "2") (pinfunction "2_2") (pintype "passive"))
      (node (ref "C20") (pin "2") (pinfunction "2_2") (pintype "passive"))
      (node (ref "C21") (pin "2") (pinfunction "2_2") (pintype "passive"))
      (node (ref "C22") (pin "2") (pinfunction "2_2") (pintype "passive"))
      (node (ref "C23") (pin "2") (pinfunction "2_2") (pintype "passive"))
      (node (ref "C24") (pin "2") (pinfunction "2_2") (pintype "passive"))
      (node (ref "C25") (pin "2") (pinfunction "2_2") (pintype "passive"))
      (node (ref "C26") (pin "2") (pinfunction "2_2") (pintype "passive"))
      (node (ref "C27") (pin "2") (pinfunction "2_2") (pintype "passive"))
      (node (ref "C28") (pin "2") (pinfunction "2_2") (pintype "passive"))
      (node (ref "C29") (pin "2") (pinfunction "2_2") (pintype "passive"))
      (node (ref "C3") (pin "2") (pinfunction "2_2") (pintype "passive"))
      (node (ref "C30") (pin "2") (pinfunction "2_2") (pintype "passive"))
      (node (ref "C31") (pin "2") (pinfunction "2_2") (pintype "passive"))
      (node (ref "C32") (pin "2") (pinfunction "2_2") (pintype "passive"))
      (node (ref "C4") (pin "1") (pinfunction "1_1") (pintype "passive"))
      (node (ref "C5") (pin "1") (pinfunction "1_1") (pintype "passive"))
      (node (ref "C6") (pin "2") (pinfunction "2_2") (pintype "passive"))
      (node (ref "C7") (pin "2") (pinfunction "2_2") (pintype "passive"))
      (node (ref "C8") (pin "2") (pinfunction "2_2") (pintype "passive"))
      (node (ref "C9") (pin "2") (pinfunction "2_2") (pintype "passive"))
      (node (ref "CL1") (pin "1") (pinfunction "1_1") (pintype "passive"))
      (node (ref "ESCL1B") (pin "1") (pinfunction "1_1") (pintype "power_in"))
      (node (ref "ESCL1C") (pin "4") (pinfunction "4_4") (pintype "passive"))
      (node (ref "ESCLA") (pin "P$4") (pinfunction "4_P$4") (pintype "passive"))
      (node (ref "IC1") (pin "12") (pinfunction "GND_12") (pintype "bidirectional"))
      (node (ref "IC1") (pin "27") (pinfunction "GND_27") (pintype "bidirectional"))
      (node (ref "IC1") (pin "3") (pinfunction "GNDA_3") (pintype "bidirectional"))
      (node (ref "IC1") (pin "32") (pinfunction "~{WAKE}_32") (pintype "bidirectional"))
      (node (ref "IC1") (pin "34") (pinfunction "XOSC0_34") (pintype "bidirectional"))
      (node (ref "IC1") (pin "35") (pinfunction "GNDX_35") (pintype "bidirectional"))
      (node (ref "IC1") (pin "39") (pinfunction "GND_39") (pintype "bidirectional"))
      (node (ref "IC1") (pin "55") (pinfunction "GND_55") (pintype "bidirectional"))
      (node (ref "JP1") (pin "19") (pinfunction "19_19") (pintype "passive"))
      (node (ref "JP1") (pin "8") (pinfunction "8_8") (pintype "passive"))
      (node (ref "JP2") (pin "12") (pinfunction "12_12") (pintype "passive"))
      (node (ref "JP2") (pin "14") (pinfunction "14_14") (pintype "passive"))
      (node (ref "JP2") (pin "16") (pinfunction "16_16") (pintype "passive"))
      (node (ref "JP2") (pin "18") (pinfunction "18_18") (pintype "passive"))
      (node (ref "JP2") (pin "19") (pinfunction "19_19") (pintype "passive"))
      (node (ref "JP2") (pin "20") (pinfunction "20_20") (pintype "passive"))
      (node (ref "JTAG") (pin "3") (pinfunction "3_3") (pintype "passive"))
      (node (ref "JTAG") (pin "5") (pinfunction "5_5") (pintype "passive"))
      (node (ref "JTAG") (pin "9") (pinfunction "9_9") (pintype "passive"))
      (node (ref "LEDS") (pin "1") (pinfunction "S_1") (pintype "passive"))
      (node (ref "PROG") (pin "1") (pinfunction "1_1") (pintype "passive"))
      (node (ref "R8") (pin "2") (pinfunction "2_2") (pintype "passive"))
      (node (ref "RST") (pin "P$1") (pinfunction "1_P$1") (pintype "passive"))
      (node (ref "S2V8") (pin "C") (pinfunction "C_C") (pintype "passive"))
      (node (ref "S3V3") (pin "C") (pinfunction "C_C") (pintype "passive"))
      (node (ref "S50V") (pin "C") (pinfunction "C_C") (pintype "passive"))
      (node (ref "U1") (pin "2") (pinfunction "GND_2") (pintype "bidirectional"))
      (node (ref "U2") (pin "2") (pinfunction "GND_2") (pintype "bidirectional"))
      (node (ref "U3") (pin "2") (pinfunction "GND_2") (pintype "bidirectional"))
      (node (ref "U4") (pin "2") (pinfunction "GND_2") (pintype "bidirectional"))
      (node (ref "U5") (pin "1") (pinfunction "GND_1") (pintype "passive"))
      (node (ref "U6") (pin "2") (pinfunction "VSS_2") (pintype "power_in"))
      (node (ref "U7") (pin "10") (pinfunction "4B_10") (pintype "input"))
      (node (ref "U7") (pin "11") (pinfunction "4A_11") (pintype "input"))
      (node (ref "U7") (pin "12") (pinfunction "4C_12") (pintype "input"))
      (node (ref "U7") (pin "6") (pinfunction "3C_6") (pintype "input"))
      (node (ref "U7") (pin "7") (pinfunction "GND_7") (pintype "power_in"))
      (node (ref "U7") (pin "8") (pinfunction "3A_8") (pintype "input"))
      (node (ref "U7") (pin "9") (pinfunction "3B_9") (pintype "input"))
      (node (ref "U8") (pin "3") (pinfunction "P$V-_3") (pintype "bidirectional"))
      (node (ref "USB") (pin "5") (pinfunction "GND_5") (pintype "bidirectional"))
      (node (ref "USB") (pin "P$1") (pinfunction "GND_P$1") (pintype "bidirectional"))
      (node (ref "USB") (pin "P$2") (pinfunction "GND_P$2") (pintype "bidirectional"))
      (node (ref "USB") (pin "P$3") (pinfunction "GND_P$3") (pintype "bidirectional"))
      (node (ref "USB") (pin "P$4") (pinfunction "GND_P$4") (pintype "bidirectional"))
    )
    (net (code "61") (name "Net-(JTAG-Pad1)") (class "Default")
      (node (ref "JTAG") (pin "1") (pinfunction "1_1") (pintype "passive"))
      (node (ref "R5") (pin "1") (pinfunction "1_1") (pintype "passive"))
    )
    (net (code "62") (name "Net-(Q3-B)") (class "Default")
      (node (ref "Q3") (pin "1") (pinfunction "B_1") (pintype "passive"))
      (node (ref "R12") (pin "2") (pinfunction "2_2") (pintype "passive"))
      (node (ref "R15") (pin "1") (pinfunction "1_1") (pintype "passive"))
    )
    (net (code "63") (name "Net-(Q3-C)") (class "Default")
      (node (ref "D1") (pin "A") (pinfunction "A_A") (pintype "passive"))
      (node (ref "Q3") (pin "3") (pinfunction "C_3") (pintype "passive"))
    )
    (net (code "64") (name "Net-(Q4-B)") (class "Default")
      (node (ref "Q4") (pin "1") (pinfunction "B_1") (pintype "passive"))
      (node (ref "R17") (pin "2") (pinfunction "2_2") (pintype "passive"))
      (node (ref "R18") (pin "1") (pinfunction "1_1") (pintype "passive"))
    )
    (net (code "65") (name "Net-(Q4-C)") (class "Default")
      (node (ref "D2") (pin "A") (pinfunction "A_A") (pintype "passive"))
      (node (ref "Q4") (pin "3") (pinfunction "C_3") (pintype "passive"))
    )
    (net (code "66") (name "Net-(Q5-B)") (class "Default")
      (node (ref "Q5") (pin "1") (pinfunction "B_1") (pintype "passive"))
      (node (ref "R19") (pin "2") (pinfunction "2_2") (pintype "passive"))
      (node (ref "R20") (pin "1") (pinfunction "1_1") (pintype "passive"))
    )
    (net (code "67") (name "Net-(Q5-C)") (class "Default")
      (node (ref "D3") (pin "A") (pinfunction "A_A") (pintype "passive"))
      (node (ref "Q5") (pin "3") (pinfunction "C_3") (pintype "passive"))
    )
    (net (code "68") (name "Net-(R11-Pad2)") (class "Default")
      (node (ref "R11") (pin "2") (pinfunction "2_2") (pintype "passive"))
      (node (ref "S3V3") (pin "A") (pinfunction "A_A") (pintype "passive"))
    )
    (net (code "69") (name "Net-(R13-Pad2)") (class "Default")
      (node (ref "R13") (pin "2") (pinfunction "2_2") (pintype "passive"))
      (node (ref "S50V") (pin "A") (pinfunction "A_A") (pintype "passive"))
    )
    (net (code "70") (name "Net-(R24-Pad2)") (class "Default")
      (node (ref "R24") (pin "2") (pinfunction "2_2") (pintype "passive"))
      (node (ref "S2V8") (pin "A") (pinfunction "A_A") (pintype "passive"))
    )
    (net (code "71") (name "Net-(RST-2)") (class "Default")
      (node (ref "C6") (pin "1") (pinfunction "1_1") (pintype "passive"))
      (node (ref "R3") (pin "2") (pinfunction "2_2") (pintype "passive"))
      (node (ref "R4") (pin "1") (pinfunction "1_1") (pintype "passive"))
      (node (ref "RST") (pin "P$2") (pinfunction "2_P$2") (pintype "passive"))
    )
    (net (code "72") (name "Net-(U1-NR{slash}FB)") (class "Default")
      (node (ref "C22") (pin "1") (pinfunction "1_1") (pintype "passive"))
      (node (ref "U1") (pin "4") (pinfunction "NR/FB_4") (pintype "bidirectional"))
    )
    (net (code "73") (name "Net-(U2-P4)") (class "Default")
      (node (ref "C24") (pin "1") (pinfunction "1_1") (pintype "passive"))
      (node (ref "U2") (pin "4") (pinfunction "P4_4") (pintype "bidirectional"))
    )
    (net (code "74") (name "Net-(U3-P4)") (class "Default")
      (node (ref "C19") (pin "1") (pinfunction "1_1") (pintype "passive"))
      (node (ref "U3") (pin "4") (pinfunction "P4_4") (pintype "bidirectional"))
    )
    (net (code "75") (name "Net-(U4-P4)") (class "Default")
      (node (ref "C26") (pin "1") (pinfunction "1_1") (pintype "passive"))
      (node (ref "U4") (pin "4") (pinfunction "P4_4") (pintype "bidirectional"))
    )
    (net (code "76") (name "Net-(U5-EN)") (class "Default")
      (node (ref "R9") (pin "1") (pinfunction "1_1") (pintype "passive"))
      (node (ref "U5") (pin "7") (pinfunction "VREF2_7") (pintype "power_in"))
      (node (ref "U5") (pin "8") (pinfunction "EN_8") (pintype "passive"))
    )
    (net (code "77") (name "Net-(U7-1A)") (class "Default")
      (node (ref "R21") (pin "1") (pinfunction "1_1") (pintype "passive"))
      (node (ref "U7") (pin "1") (pinfunction "1A_1") (pintype "input"))
    )
    (net (code "78") (name "Net-(U7-2A)") (class "Default")
      (node (ref "R16") (pin "1") (pinfunction "1_1") (pintype "passive"))
      (node (ref "U7") (pin "4") (pinfunction "2A_4") (pintype "input"))
    )
    (net (code "79") (name "Net-(U8A-A)") (class "Default")
      (node (ref "SJ3") (pin "2") (pinfunction "2_2") (pintype "passive"))
      (node (ref "U8") (pin "2") (pinfunction "A_2") (pintype "bidirectional"))
    )
    (net (code "80") (name "Net-(USB-ID)") (class "Default")
      (node (ref "R1") (pin "2") (pinfunction "2_2") (pintype "passive"))
      (node (ref "USB") (pin "4") (pinfunction "ID_4") (pintype "bidirectional"))
    )
    (net (code "81") (name "unconnected-(IC1-XOSC1-Pad36)") (class "Default")
      (node (ref "IC1") (pin "36") (pinfunction "XOSC1_36") (pintype "bidirectional"))
    )
    (net (code "82") (name "unconnected-(IC1-~{HIB}-Pad33)") (class "Default")
      (node (ref "IC1") (pin "33") (pinfunction "~{HIB}_33") (pintype "bidirectional"))
    )
    (net (code "83") (name "unconnected-(JTAG-Pad7)") (class "Default")
      (node (ref "JTAG") (pin "7") (pinfunction "7_7") (pintype "passive"))
    )
  )
)
